# Esquema_NTC.net
KiCad netlist of a schematic drawn in Altium Designer
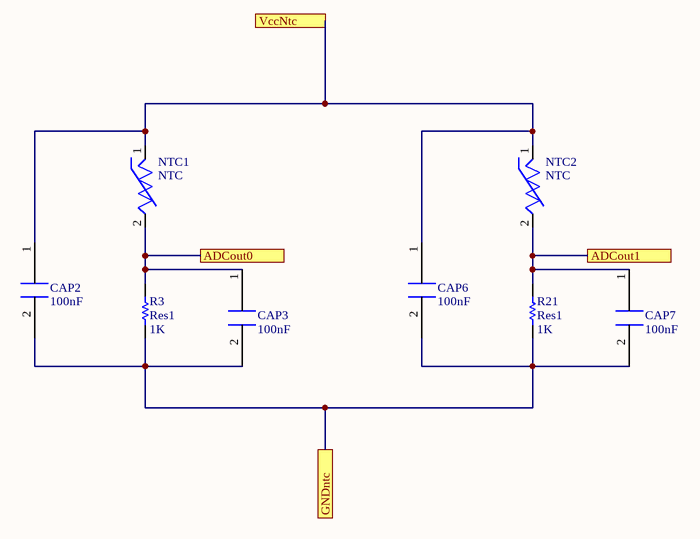
[diagram p0: Esquema NTC.SchDoc]

(export (version "E")
  (design (tool "Eeschema 10.0.6"))
  (components
    (comp (ref "CAP2")
      (value "100nF")
      (footprint "Capacitor Eletro")
      (description "Condensador")
      (libsource (lib "myLibAltium") (part "33pF"))
    )
    (comp (ref "CAP3")
      (value "100nF")
      (footprint "Capacitor Eletro")
      (description "Condensador")
      (libsource (lib "myLibAltium") (part "33pF"))
    )
    (comp (ref "CAP6")
      (value "100nF")
      (footprint "Capacitor Eletro")
      (description "Condensador")
      (libsource (lib "myLibAltium") (part "33pF"))
    )
    (comp (ref "CAP7")
      (value "100nF")
      (footprint "Capacitor Eletro")
      (description "Condensador")
      (libsource (lib "myLibAltium") (part "33pF"))
    )
    (comp (ref "NTC1") (value "NTC") (footprint "NTC") (libsource (lib "myLibAltium") (part "NTC")))
    (comp (ref "NTC2") (value "NTC") (footprint "NTC") (libsource (lib "myLibAltium") (part "NTC")))
    (comp (ref "R3")
      (value "Res1")
      (footprint "AXIAL-0.3")
      (description "Resistor")
      (fields (field (name "ALTIUM_VALUE") "1K") (field (name "PUBLISHER") "Altium Limited"))
      (libsource (lib "Miscellaneous Devices") (part "Res1"))
    )
    (comp (ref "R21")
      (value "Res1")
      (footprint "AXIAL-0.3")
      (description "Resistor")
      (fields (field (name "ALTIUM_VALUE") "1K") (field (name "PUBLISHER") "Altium Limited"))
      (libsource (lib "Miscellaneous Devices") (part "Res1"))
    )
  )
  (nets
    (net (code "1") (name "/ADCout0") (class "Default")
      (node (ref "CAP3") (pin "1") (pintype "passive"))
      (node (ref "NTC1") (pin "2") (pinfunction "2_2") (pintype "passive"))
      (node (ref "R3") (pin "2") (pinfunction "2_2") (pintype "passive"))
    )
    (net (code "2") (name "/ADCout1") (class "Default")
      (node (ref "CAP7") (pin "1") (pintype "passive"))
      (node (ref "NTC2") (pin "2") (pinfunction "2_2") (pintype "passive"))
      (node (ref "R21") (pin "2") (pinfunction "2_2") (pintype "passive"))
    )
    (net (code "3") (name "/GNDntc") (class "Default")
      (node (ref "CAP2") (pin "2") (pintype "passive"))
      (node (ref "CAP3") (pin "2") (pintype "passive"))
      (node (ref "CAP6") (pin "2") (pintype "passive"))
      (node (ref "CAP7") (pin "2") (pintype "passive"))
      (node (ref "R21") (pin "1") (pinfunction "1_1") (pintype "passive"))
      (node (ref "R3") (pin "1") (pinfunction "1_1") (pintype "passive"))
    )
    (net (code "4") (name "/VccNtc") (class "Default")
      (node (ref "CAP2") (pin "1") (pintype "passive"))
      (node (ref "CAP6") (pin "1") (pintype "passive"))
      (node (ref "NTC1") (pin "1") (pinfunction "1_1") (pintype "passive"))
      (node (ref "NTC2") (pin "1") (pinfunction "1_1") (pintype "passive"))
    )
  )
)
